# encoder__EDA.net
KiCad netlist of a schematic drawn in EasyEDA
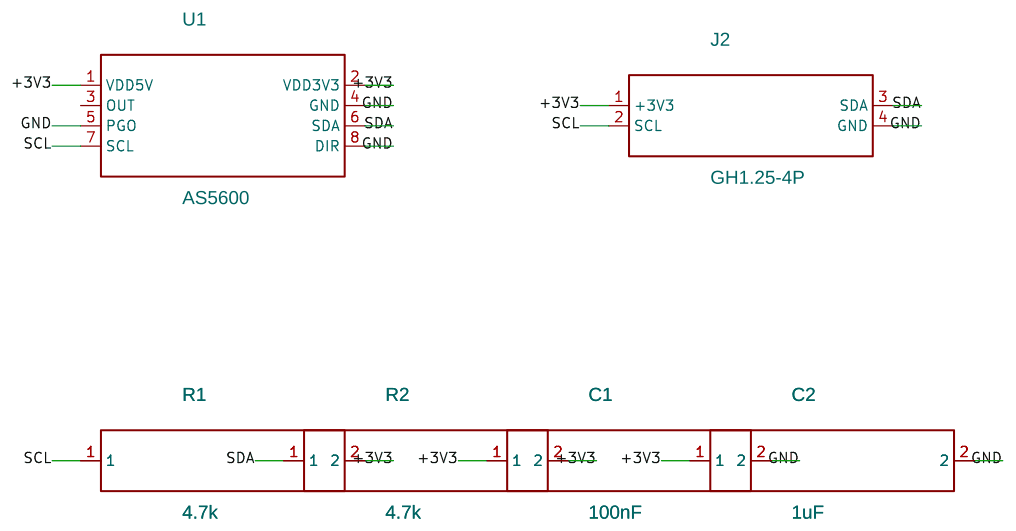
[diagram p0: schematic sheet]

(export (version "E")
  (design (tool "Eeschema 10.0.6"))
  (components
    (comp (ref "C1") (value "100nF") (libsource (lib "") (part "Unknown_500_470")))
    (comp (ref "C2") (value "1uF") (libsource (lib "") (part "Unknown_600_470")))
    (comp (ref "J2") (value "GH1.25-4P") (libsource (lib "") (part "Unknown_560_300")))
    (comp (ref "R1") (value "4.7k") (libsource (lib "") (part "Unknown_300_470")))
    (comp (ref "R2") (value "4.7k") (libsource (lib "") (part "Unknown_400_470")))
    (comp (ref "U1") (value "AS5600") (libsource (lib "") (part "Unknown_300_300")))
  )
  (nets
    (net (code "1") (name "/+3V3") (class "Default")
      (node (ref "C1") (pin "1") (pinfunction "1_1") (pintype "unspecified"))
      (node (ref "C2") (pin "1") (pinfunction "1_1") (pintype "unspecified"))
      (node (ref "J2") (pin "1") (pinfunction "+3V3_1") (pintype "unspecified"))
      (node (ref "R1") (pin "2") (pinfunction "2_2") (pintype "unspecified"))
      (node (ref "R2") (pin "2") (pinfunction "2_2") (pintype "unspecified"))
      (node (ref "U1") (pin "1") (pinfunction "VDD5V_1") (pintype "unspecified"))
      (node (ref "U1") (pin "2") (pinfunction "VDD3V3_2") (pintype "unspecified"))
    )
    (net (code "2") (name "/GND") (class "Default")
      (node (ref "C1") (pin "2") (pinfunction "2_2") (pintype "unspecified"))
      (node (ref "C2") (pin "2") (pinfunction "2_2") (pintype "unspecified"))
      (node (ref "J2") (pin "4") (pinfunction "GND_4") (pintype "unspecified"))
      (node (ref "U1") (pin "4") (pinfunction "GND_4") (pintype "unspecified"))
      (node (ref "U1") (pin "5") (pinfunction "PGO_5") (pintype "unspecified"))
      (node (ref "U1") (pin "8") (pinfunction "DIR_8") (pintype "unspecified"))
    )
    (net (code "3") (name "/SCL") (class "Default")
      (node (ref "J2") (pin "2") (pinfunction "SCL_2") (pintype "unspecified"))
      (node (ref "R1") (pin "1") (pinfunction "1_1") (pintype "unspecified"))
      (node (ref "U1") (pin "7") (pinfunction "SCL_7") (pintype "unspecified"))
    )
    (net (code "4") (name "/SDA") (class "Default")
      (node (ref "J2") (pin "3") (pinfunction "SDA_3") (pintype "unspecified"))
      (node (ref "R2") (pin "1") (pinfunction "1_1") (pintype "unspecified"))
      (node (ref "U1") (pin "6") (pinfunction "SDA_6") (pintype "unspecified"))
    )
    (net (code "5") (name "unconnected-(U1-OUT-Pad3)") (class "Default")
      (node (ref "U1") (pin "3") (pinfunction "OUT_3") (pintype "unspecified"))
    )
  )
)
